# teensy.net
KiCad netlist of a schematic drawn in EAGLE
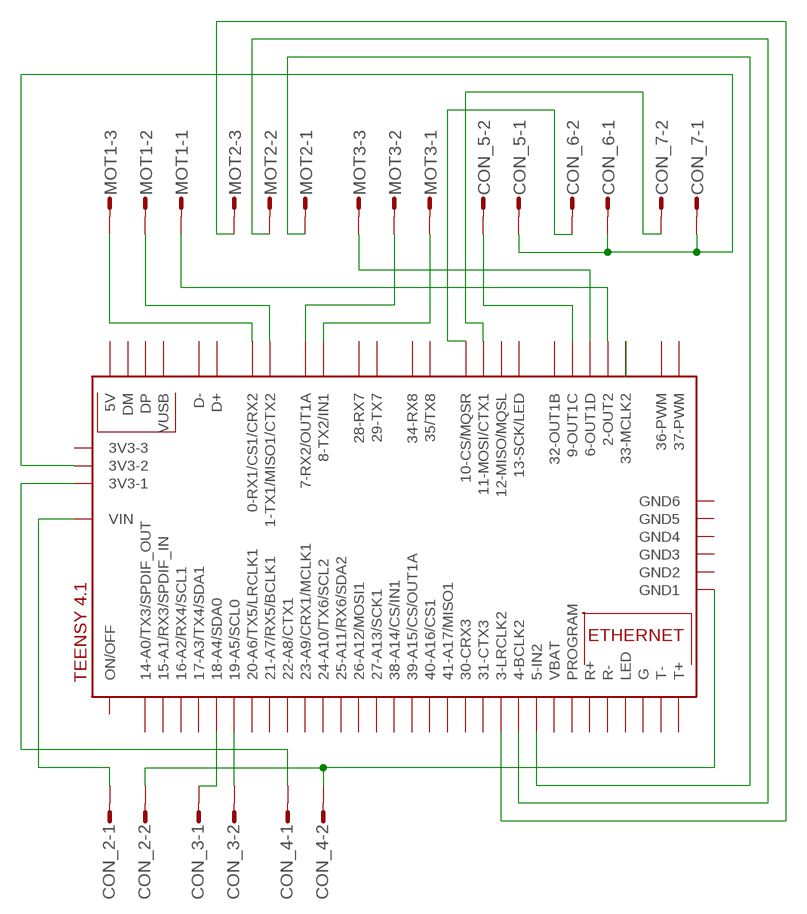
[diagram p0: schematic, sheet 1]

(export (version "E")
  (design (tool "Eeschema 10.0.6"))
  (components
    (comp (ref "CON_2")
      (value "S02P")
      (footprint "eagle-import:S02P")
      (libsource (lib "eagle-import") (part "S02P"))
    )
    (comp (ref "CON_3")
      (value "S02P")
      (footprint "eagle-import:S02P")
      (libsource (lib "eagle-import") (part "S02P"))
    )
    (comp (ref "CON_4")
      (value "S02P")
      (footprint "eagle-import:S02P")
      (libsource (lib "eagle-import") (part "S02P"))
    )
    (comp (ref "CON_5")
      (value "S02P")
      (footprint "eagle-import:S02P")
      (libsource (lib "eagle-import") (part "S02P"))
    )
    (comp (ref "CON_6")
      (value "S02P")
      (footprint "eagle-import:S02P")
      (libsource (lib "eagle-import") (part "S02P"))
    )
    (comp (ref "CON_7")
      (value "S02P")
      (footprint "eagle-import:S02P")
      (libsource (lib "eagle-import") (part "S02P"))
    )
    (comp (ref "MOT1")
      (value "S03P")
      (footprint "eagle-import:S03P")
      (libsource (lib "eagle-import") (part "S03P"))
    )
    (comp (ref "MOT2")
      (value "S03P")
      (footprint "eagle-import:S03P")
      (libsource (lib "eagle-import") (part "S03P"))
    )
    (comp (ref "MOT3")
      (value "S03P")
      (footprint "eagle-import:S03P")
      (libsource (lib "eagle-import") (part "S03P"))
    )
    (comp (ref "U$1")
      (value "TEENSY41")
      (footprint "eagle-import:TEENSY41")
      (libsource (lib "eagle-import") (part "TEENSY41"))
    )
  )
  (nets
    (net (code "1") (name "Net-(CON_2A-S)") (class "Default")
      (node (ref "CON_2") (pin "1") (pinfunction "S_1") (pintype "passive"))
      (node (ref "U$1") (pin "VIN") (pinfunction "VIN_VIN") (pintype "bidirectional"))
    )
    (net (code "2") (name "Net-(CON_2B-S)") (class "Default")
      (node (ref "CON_2") (pin "2") (pinfunction "S_2") (pintype "passive"))
      (node (ref "CON_4") (pin "2") (pinfunction "S_2") (pintype "passive"))
      (node (ref "U$1") (pin "GND1") (pinfunction "GND1_GND1") (pintype "bidirectional"))
    )
    (net (code "3") (name "Net-(CON_3A-S)") (class "Default")
      (node (ref "CON_3") (pin "1") (pinfunction "S_1") (pintype "passive"))
      (node (ref "U$1") (pin "18-A4/SDA0") (pinfunction "18-A4/SDA0_18-A4/SDA0") (pintype "bidirectional"))
    )
    (net (code "4") (name "Net-(CON_3B-S)") (class "Default")
      (node (ref "CON_3") (pin "2") (pinfunction "S_2") (pintype "passive"))
      (node (ref "U$1") (pin "19-A5/SCL0") (pinfunction "19-A5/SCL0_19-A5/SCL0") (pintype "bidirectional"))
    )
    (net (code "5") (name "Net-(CON_4A-S)") (class "Default")
      (node (ref "CON_4") (pin "1") (pinfunction "S_1") (pintype "passive"))
      (node (ref "U$1") (pin "3V3-1") (pinfunction "3V3-1_3V3-1") (pintype "bidirectional"))
    )
    (net (code "6") (name "Net-(CON_5A-S)") (class "Default")
      (node (ref "CON_5") (pin "1") (pinfunction "S_1") (pintype "passive"))
      (node (ref "CON_6") (pin "1") (pinfunction "S_1") (pintype "passive"))
      (node (ref "CON_7") (pin "1") (pinfunction "S_1") (pintype "passive"))
      (node (ref "U$1") (pin "3V3-2") (pinfunction "3V3-2_3V3-2") (pintype "bidirectional"))
    )
    (net (code "7") (name "Net-(CON_5B-S)") (class "Default")
      (node (ref "CON_5") (pin "2") (pinfunction "S_2") (pintype "passive"))
      (node (ref "U$1") (pin "9-OUT1C") (pinfunction "9-OUT1C_9-OUT1C") (pintype "bidirectional"))
    )
    (net (code "8") (name "Net-(CON_6B-S)") (class "Default")
      (node (ref "CON_6") (pin "2") (pinfunction "S_2") (pintype "passive"))
      (node (ref "U$1") (pin "10-CS\\MQSR") (pinfunction "10-CS/MQSR_10-CS\\MQSR") (pintype "bidirectional"))
    )
    (net (code "9") (name "Net-(CON_7B-S)") (class "Default")
      (node (ref "CON_7") (pin "2") (pinfunction "S_2") (pintype "passive"))
      (node (ref "U$1") (pin "11-MOSI/CTX1") (pinfunction "11-MOSI/CTX1_11-MOSI/CTX1") (pintype "bidirectional"))
    )
    (net (code "10") (name "Net-(MOT1A-S)") (class "Default")
      (node (ref "MOT1") (pin "1") (pinfunction "S_1") (pintype "passive"))
      (node (ref "U$1") (pin "2-OUT2") (pinfunction "2-OUT2_2-OUT2") (pintype "bidirectional"))
    )
    (net (code "11") (name "Net-(MOT1B-S)") (class "Default")
      (node (ref "MOT1") (pin "2") (pinfunction "S_2") (pintype "passive"))
      (node (ref "U$1") (pin "1-TX1/MISO1/CTX2") (pinfunction "1-TX1/MISO1/CTX2_1-TX1/MISO1/CTX2") (pintype "bidirectional"))
    )
    (net (code "12") (name "Net-(MOT1C-S)") (class "Default")
      (node (ref "MOT1") (pin "3") (pinfunction "S_3") (pintype "passive"))
      (node (ref "U$1") (pin "0-RX1/CS1/CRX2") (pinfunction "0-RX1/CS1/CRX2_0-RX1/CS1/CRX2") (pintype "bidirectional"))
    )
    (net (code "13") (name "Net-(MOT2A-S)") (class "Default")
      (node (ref "MOT2") (pin "1") (pinfunction "S_1") (pintype "passive"))
      (node (ref "U$1") (pin "5-IN2") (pinfunction "5-IN2_5-IN2") (pintype "bidirectional"))
    )
    (net (code "14") (name "Net-(MOT2B-S)") (class "Default")
      (node (ref "MOT2") (pin "2") (pinfunction "S_2") (pintype "passive"))
      (node (ref "U$1") (pin "4-BCLK2") (pinfunction "4-BCLK2_4-BCLK2") (pintype "bidirectional"))
    )
    (net (code "15") (name "Net-(MOT2C-S)") (class "Default")
      (node (ref "MOT2") (pin "3") (pinfunction "S_3") (pintype "passive"))
      (node (ref "U$1") (pin "3-LRCLK2") (pinfunction "3-LRCLK2_3-LRCLK2") (pintype "bidirectional"))
    )
    (net (code "16") (name "Net-(MOT3A-S)") (class "Default")
      (node (ref "MOT3") (pin "1") (pinfunction "S_1") (pintype "passive"))
      (node (ref "U$1") (pin "8-TX2/IN1") (pinfunction "8-TX2/IN1_8-TX2/IN1") (pintype "bidirectional"))
    )
    (net (code "17") (name "Net-(MOT3B-S)") (class "Default")
      (node (ref "MOT3") (pin "2") (pinfunction "S_2") (pintype "passive"))
      (node (ref "U$1") (pin "7-RX2/OUT1A") (pinfunction "7-RX2/OUT1A_7-RX2/OUT1A") (pintype "bidirectional"))
    )
    (net (code "18") (name "Net-(MOT3C-S)") (class "Default")
      (node (ref "MOT3") (pin "3") (pinfunction "S_3") (pintype "passive"))
      (node (ref "U$1") (pin "6-OUT1D") (pinfunction "6-OUT1D_6-OUT1D") (pintype "bidirectional"))
    )
    (net (code "19") (name "unconnected-(U$1-5V-Pad+5V)") (class "Default")
      (node (ref "U$1") (pin "+5V") (pinfunction "5V_+5V") (pintype "bidirectional"))
    )
    (net (code "20") (name "unconnected-(U$1-35{slash}TX8-Pad35-TX8)") (class "Default")
      (node (ref "U$1") (pin "35-TX8") (pinfunction "35/TX8_35-TX8") (pintype "bidirectional"))
    )
    (net (code "21") (name "unconnected-(U$1-Pad3V3-3)") (class "Default")
      (node (ref "U$1") (pin "3V3-3") (pinfunction "3V3-3_3V3-3") (pintype "bidirectional"))
    )
    (net (code "22") (name "unconnected-(U$1-Pad12-MISO{slash}MQSL)") (class "Default")
      (node (ref "U$1") (pin "12-MISO/MQSL") (pinfunction "12-MISO/MQSL_12-MISO/MQSL") (pintype "bidirectional"))
    )
    (net (code "23") (name "unconnected-(U$1-Pad13-SCK{slash}LED)") (class "Default")
      (node (ref "U$1") (pin "13-SCK/LED") (pinfunction "13-SCK/LED_13-SCK/LED") (pintype "bidirectional"))
    )
    (net (code "24") (name "unconnected-(U$1-Pad14-A0{slash}TX3{slash}SPDIF_OUT)") (class "Default")
      (node (ref "U$1") (pin "14-A0/TX3/SPDIF_OUT") (pinfunction "14-A0/TX3/SPDIF_OUT_14-A0/TX3/SPDIF_OUT") (pintype "bidirectional"))
    )
    (net (code "25") (name "unconnected-(U$1-Pad15-A1{slash}RX3{slash}SPDIF_IN)") (class "Default")
      (node (ref "U$1") (pin "15-A1/RX3/SPDIF_IN") (pinfunction "15-A1/RX3/SPDIF_IN_15-A1/RX3/SPDIF_IN") (pintype "bidirectional"))
    )
    (net (code "26") (name "unconnected-(U$1-Pad16-A2{slash}RX4{slash}SCL1)") (class "Default")
      (node (ref "U$1") (pin "16-A2/RX4/SCL1") (pinfunction "16-A2/RX4/SCL1_16-A2/RX4/SCL1") (pintype "bidirectional"))
    )
    (net (code "27") (name "unconnected-(U$1-Pad17-A3{slash}TX4{slash}SDA1)") (class "Default")
      (node (ref "U$1") (pin "17-A3/TX4/SDA1") (pinfunction "17-A3/TX4/SDA1_17-A3/TX4/SDA1") (pintype "bidirectional"))
    )
    (net (code "28") (name "unconnected-(U$1-Pad20-A6{slash}TX5{slash}LRCLK1)") (class "Default")
      (node (ref "U$1") (pin "20-A6/TX5/LRCLK1") (pinfunction "20-A6/TX5/LRCLK1_20-A6/TX5/LRCLK1") (pintype "bidirectional"))
    )
    (net (code "29") (name "unconnected-(U$1-Pad21-A7{slash}RX5{slash}BCLK1)") (class "Default")
      (node (ref "U$1") (pin "21-A7/RX5/BCLK1") (pinfunction "21-A7/RX5/BCLK1_21-A7/RX5/BCLK1") (pintype "bidirectional"))
    )
    (net (code "30") (name "unconnected-(U$1-Pad22-A8{slash}CTX1)") (class "Default")
      (node (ref "U$1") (pin "22-A8/CTX1") (pinfunction "22-A8/CTX1_22-A8/CTX1") (pintype "bidirectional"))
    )
    (net (code "31") (name "unconnected-(U$1-Pad23-A9{slash}CRX1{slash}MCLK1)") (class "Default")
      (node (ref "U$1") (pin "23-A9/CRX1/MCLK1") (pinfunction "23-A9/CRX1/MCLK1_23-A9/CRX1/MCLK1") (pintype "bidirectional"))
    )
    (net (code "32") (name "unconnected-(U$1-Pad24-A10{slash}TX6{slash}SCL2)") (class "Default")
      (node (ref "U$1") (pin "24-A10/TX6/SCL2") (pinfunction "24-A10/TX6/SCL2_24-A10/TX6/SCL2") (pintype "bidirectional"))
    )
    (net (code "33") (name "unconnected-(U$1-Pad25-A11{slash}RX6{slash}SDA2)") (class "Default")
      (node (ref "U$1") (pin "25-A11/RX6/SDA2") (pinfunction "25-A11/RX6/SDA2_25-A11/RX6/SDA2") (pintype "bidirectional"))
    )
    (net (code "34") (name "unconnected-(U$1-Pad26-A12{slash}MOSI1)") (class "Default")
      (node (ref "U$1") (pin "26-A12/MOSI1") (pinfunction "26-A12/MOSI1_26-A12/MOSI1") (pintype "bidirectional"))
    )
    (net (code "35") (name "unconnected-(U$1-Pad27-A13{slash}SCK1)") (class "Default")
      (node (ref "U$1") (pin "27-A13/SCK1") (pinfunction "27-A13/SCK1_27-A13/SCK1") (pintype "bidirectional"))
    )
    (net (code "36") (name "unconnected-(U$1-Pad28-RX7)") (class "Default")
      (node (ref "U$1") (pin "28-RX7") (pinfunction "28-RX7_28-RX7") (pintype "bidirectional"))
    )
    (net (code "37") (name "unconnected-(U$1-Pad29-TX7)") (class "Default")
      (node (ref "U$1") (pin "29-TX7") (pinfunction "29-TX7_29-TX7") (pintype "bidirectional"))
    )
    (net (code "38") (name "unconnected-(U$1-Pad30-CRX3)") (class "Default")
      (node (ref "U$1") (pin "30-CRX3") (pinfunction "30-CRX3_30-CRX3") (pintype "bidirectional"))
    )
    (net (code "39") (name "unconnected-(U$1-Pad31-CTX3)") (class "Default")
      (node (ref "U$1") (pin "31-CTX3") (pinfunction "31-CTX3_31-CTX3") (pintype "bidirectional"))
    )
    (net (code "40") (name "unconnected-(U$1-Pad32-OUT1B)") (class "Default")
      (node (ref "U$1") (pin "32-OUT1B") (pinfunction "32-OUT1B_32-OUT1B") (pintype "bidirectional"))
    )
    (net (code "41") (name "unconnected-(U$1-Pad33-MCLK2)") (class "Default")
      (node (ref "U$1") (pin "33-MCLK2") (pinfunction "33-MCLK2_33-MCLK2") (pintype "bidirectional"))
    )
    (net (code "42") (name "unconnected-(U$1-Pad34-RX8)") (class "Default")
      (node (ref "U$1") (pin "34-RX8") (pinfunction "34-RX8_34-RX8") (pintype "bidirectional"))
    )
    (net (code "43") (name "unconnected-(U$1-Pad36-PWM)") (class "Default")
      (node (ref "U$1") (pin "36-PWM") (pinfunction "36-PWM_36-PWM") (pintype "bidirectional"))
    )
    (net (code "44") (name "unconnected-(U$1-Pad37-PWM)") (class "Default")
      (node (ref "U$1") (pin "37-PWM") (pinfunction "37-PWM_37-PWM") (pintype "bidirectional"))
    )
    (net (code "45") (name "unconnected-(U$1-Pad38-A14{slash}CS{slash}IN1)") (class "Default")
      (node (ref "U$1") (pin "38-A14/CS/IN1") (pinfunction "38-A14/CS/IN1_38-A14/CS/IN1") (pintype "bidirectional"))
    )
    (net (code "46") (name "unconnected-(U$1-Pad39-A15{slash}CS{slash}OUT1A)") (class "Default")
      (node (ref "U$1") (pin "39-A15/CS/OUT1A") (pinfunction "39-A15/CS/OUT1A_39-A15/CS/OUT1A") (pintype "bidirectional"))
    )
    (net (code "47") (name "unconnected-(U$1-Pad40-A16{slash}CS1)") (class "Default")
      (node (ref "U$1") (pin "40-A16/CS1") (pinfunction "40-A16/CS1_40-A16/CS1") (pintype "bidirectional"))
    )
    (net (code "48") (name "unconnected-(U$1-Pad41-A17{slash}MISO1)") (class "Default")
      (node (ref "U$1") (pin "41-A17/MISO1") (pinfunction "41-A17/MISO1_41-A17/MISO1") (pintype "bidirectional"))
    )
    (net (code "49") (name "unconnected-(U$1-PadD+)") (class "Default")
      (node (ref "U$1") (pin "D+") (pinfunction "D+_D+") (pintype "bidirectional"))
    )
    (net (code "50") (name "unconnected-(U$1-PadD-)") (class "Default")
      (node (ref "U$1") (pin "D-") (pinfunction "D-_D-") (pintype "bidirectional"))
    )
    (net (code "51") (name "unconnected-(U$1-PadDM)") (class "Default")
      (node (ref "U$1") (pin "DM") (pinfunction "DM_DM") (pintype "bidirectional"))
    )
    (net (code "52") (name "unconnected-(U$1-PadDP)") (class "Default")
      (node (ref "U$1") (pin "DP") (pinfunction "DP_DP") (pintype "bidirectional"))
    )
    (net (code "53") (name "unconnected-(U$1-PadG)") (class "Default")
      (node (ref "U$1") (pin "G") (pinfunction "G_G") (pintype "bidirectional"))
    )
    (net (code "54") (name "unconnected-(U$1-PadGND2)") (class "Default")
      (node (ref "U$1") (pin "GND2") (pinfunction "GND2_GND2") (pintype "bidirectional"))
    )
    (net (code "55") (name "unconnected-(U$1-PadGND3)") (class "Default")
      (node (ref "U$1") (pin "GND3") (pinfunction "GND3_GND3") (pintype "bidirectional"))
    )
    (net (code "56") (name "unconnected-(U$1-PadGND4)") (class "Default")
      (node (ref "U$1") (pin "GND4") (pinfunction "GND4_GND4") (pintype "bidirectional"))
    )
    (net (code "57") (name "unconnected-(U$1-PadGND5)") (class "Default")
      (node (ref "U$1") (pin "GND5") (pinfunction "GND5_GND5") (pintype "bidirectional"))
    )
    (net (code "58") (name "unconnected-(U$1-PadGND6)") (class "Default")
      (node (ref "U$1") (pin "GND6") (pinfunction "GND6_GND6") (pintype "bidirectional"))
    )
    (net (code "59") (name "unconnected-(U$1-PadLED)") (class "Default")
      (node (ref "U$1") (pin "LED") (pinfunction "LED_LED") (pintype "bidirectional"))
    )
    (net (code "60") (name "unconnected-(U$1-PadON{slash}OFF)") (class "Default")
      (node (ref "U$1") (pin "ON/OFF") (pinfunction "ON/OFF_ON/OFF") (pintype "bidirectional"))
    )
    (net (code "61") (name "unconnected-(U$1-PadPROGRAM)") (class "Default")
      (node (ref "U$1") (pin "PROGRAM") (pinfunction "PROGRAM_PROGRAM") (pintype "bidirectional"))
    )
    (net (code "62") (name "unconnected-(U$1-PadR+)") (class "Default")
      (node (ref "U$1") (pin "R+") (pinfunction "R+_R+") (pintype "bidirectional"))
    )
    (net (code "63") (name "unconnected-(U$1-PadR-)") (class "Default")
      (node (ref "U$1") (pin "R-") (pinfunction "R-_R-") (pintype "bidirectional"))
    )
    (net (code "64") (name "unconnected-(U$1-PadT+)") (class "Default")
      (node (ref "U$1") (pin "T+") (pinfunction "T+_T+") (pintype "bidirectional"))
    )
    (net (code "65") (name "unconnected-(U$1-PadT-)") (class "Default")
      (node (ref "U$1") (pin "T-") (pinfunction "T-_T-") (pintype "bidirectional"))
    )
    (net (code "66") (name "unconnected-(U$1-PadVBAT)") (class "Default")
      (node (ref "U$1") (pin "VBAT") (pinfunction "VBAT_VBAT") (pintype "bidirectional"))
    )
    (net (code "67") (name "unconnected-(U$1-PadVUSB)") (class "Default")
      (node (ref "U$1") (pin "VUSB") (pinfunction "VUSB_VUSB") (pintype "bidirectional"))
    )
  )
)
